# cp2101-esp32.net
KiCad netlist of a schematic drawn in EAGLE
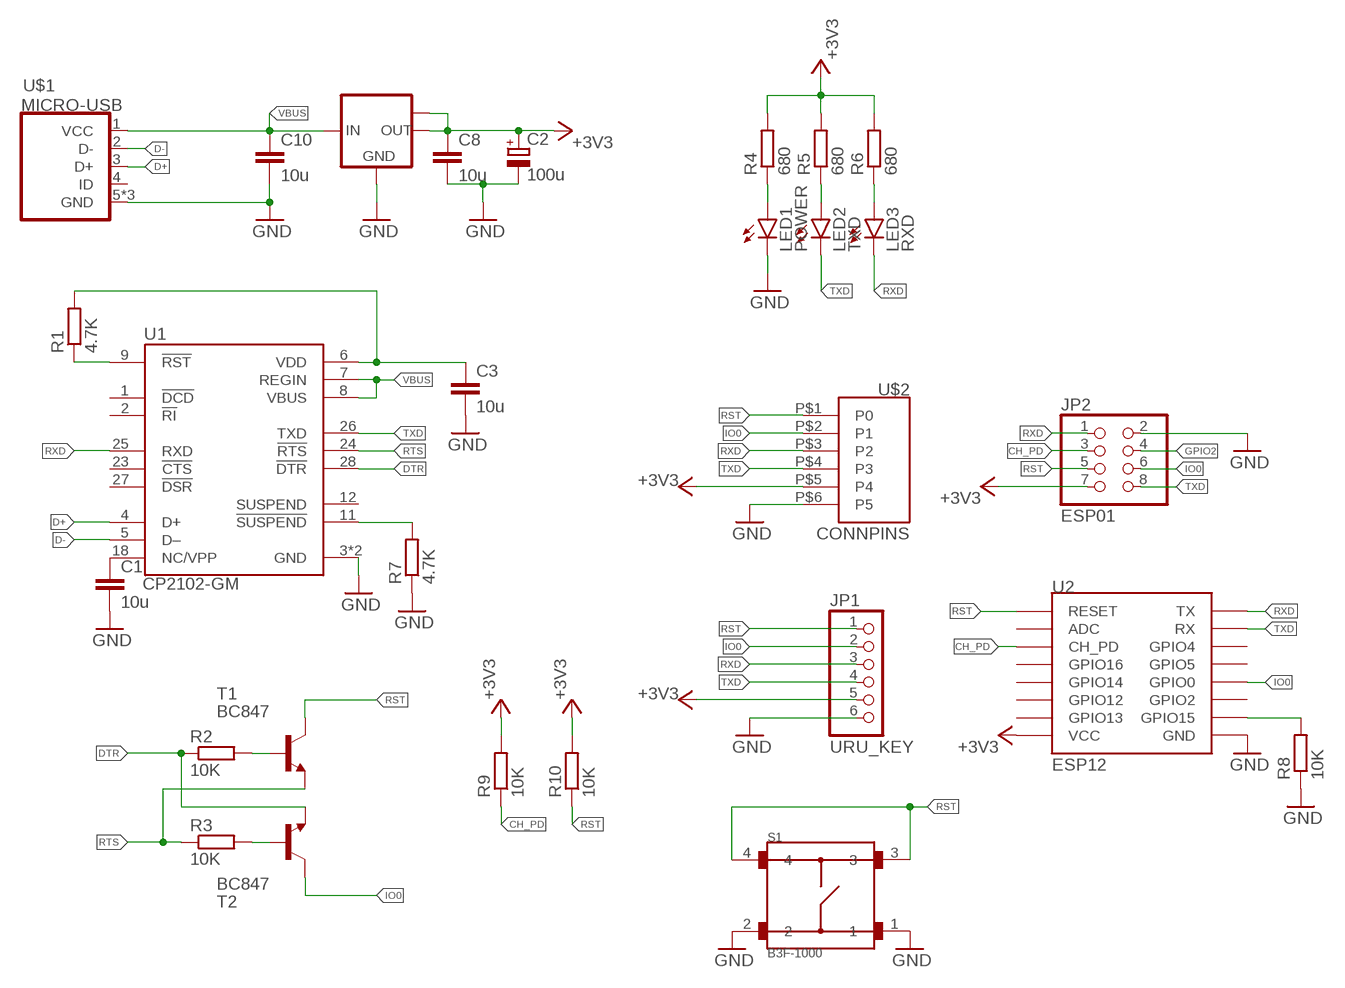
[diagram p0: schematic, sheet 1]

(export (version "E")
  (design (tool "Eeschema 10.0.6"))
  (components
    (comp (ref "C1")
      (value "10u")
      (footprint "eagle-import:C0805")
      (libsource (lib "eagle-import") (part "C-EUC0805"))
    )
    (comp (ref "C2")
      (value "100u")
      (footprint "eagle-import:A_3216-18R")
      (libsource (lib "eagle-import") (part "CPOL-EUA/3216-18R"))
    )
    (comp (ref "C3")
      (value "10u")
      (footprint "eagle-import:C0805")
      (libsource (lib "eagle-import") (part "C-EUC0805"))
    )
    (comp (ref "C8")
      (value "10u")
      (footprint "eagle-import:C0805")
      (libsource (lib "eagle-import") (part "C-EUC0805"))
    )
    (comp (ref "C10")
      (value "10u")
      (footprint "eagle-import:C0805")
      (libsource (lib "eagle-import") (part "C-EUC0805"))
    )
    (comp (ref "IC1")
      (value "LM1117MPX-3.3")
      (footprint "eagle-import:SOT223")
      (libsource (lib "eagle-import") (part "LM1117MPX-3.3"))
    )
    (comp (ref "JP1")
      (value "URU_KEY")
      (footprint "eagle-import:1X06_90")
      (libsource (lib "eagle-import") (part "PINHD-1X6/90"))
    )
    (comp (ref "JP2")
      (value "ESP01")
      (footprint "eagle-import:2X04")
      (libsource (lib "eagle-import") (part "PINHD-2X4"))
    )
    (comp (ref "LED1")
      (value "POWER")
      (footprint "eagle-import:CHIP-LED0805")
      (libsource (lib "eagle-import") (part "LEDCHIP-LED0805"))
    )
    (comp (ref "LED2")
      (value "TXD")
      (footprint "eagle-import:CHIP-LED0805")
      (libsource (lib "eagle-import") (part "LEDCHIP-LED0805"))
    )
    (comp (ref "LED3")
      (value "RXD")
      (footprint "eagle-import:CHIP-LED0805")
      (libsource (lib "eagle-import") (part "LEDCHIP-LED0805"))
    )
    (comp (ref "R1")
      (value "4.7K")
      (footprint "eagle-import:R0805")
      (libsource (lib "eagle-import") (part "R-EU_R0805"))
    )
    (comp (ref "R2")
      (value "10K")
      (footprint "eagle-import:R0805")
      (libsource (lib "eagle-import") (part "R-EU_R0805"))
    )
    (comp (ref "R3")
      (value "10K")
      (footprint "eagle-import:R0805")
      (libsource (lib "eagle-import") (part "R-EU_R0805"))
    )
    (comp (ref "R4")
      (value "680")
      (footprint "eagle-import:R0805")
      (libsource (lib "eagle-import") (part "R-EU_R0805"))
    )
    (comp (ref "R5")
      (value "680")
      (footprint "eagle-import:R0805")
      (libsource (lib "eagle-import") (part "R-EU_R0805"))
    )
    (comp (ref "R6")
      (value "680")
      (footprint "eagle-import:R0805")
      (libsource (lib "eagle-import") (part "R-EU_R0805"))
    )
    (comp (ref "R7")
      (value "4.7K")
      (footprint "eagle-import:R0805")
      (libsource (lib "eagle-import") (part "R-EU_R0805"))
    )
    (comp (ref "R8")
      (value "10K")
      (footprint "eagle-import:R0805")
      (libsource (lib "eagle-import") (part "R-EU_R0805"))
    )
    (comp (ref "R9")
      (value "10K")
      (footprint "eagle-import:R0805")
      (libsource (lib "eagle-import") (part "R-EU_R0805"))
    )
    (comp (ref "R10")
      (value "10K")
      (footprint "eagle-import:R0805")
      (libsource (lib "eagle-import") (part "R-EU_R0805"))
    )
    (comp (ref "S1")
      (value "B3F-1000")
      (footprint "eagle-import:SW_B3F-1000")
      (fields (field (name "MF") "Omron"))
      (libsource (lib "eagle-import") (part "B3F-1000"))
    )
    (comp (ref "T1")
      (value "BC847")
      (footprint "eagle-import:SOT23")
      (libsource (lib "eagle-import") (part "BC847"))
    )
    (comp (ref "T2")
      (value "BC847")
      (footprint "eagle-import:SOT23")
      (libsource (lib "eagle-import") (part "BC847"))
    )
    (comp (ref "U$1")
      (value "MICRO-USB")
      (footprint "eagle-import:MICRO-USB")
      (libsource (lib "eagle-import") (part "MICRO-USB"))
    )
    (comp (ref "U$2")
      (value "CONNPINS")
      (footprint "eagle-import:PINS")
      (libsource (lib "eagle-import") (part "CONNPINS"))
    )
    (comp (ref "U1")
      (value "CP2102-GM")
      (footprint "eagle-import:QFN50P500X500X100-29N")
      (fields (field (name "MF") "Silicon Labs"))
      (libsource (lib "eagle-import") (part "CP2102-GM"))
    )
    (comp (ref "U2")
      (value "ESP12")
      (footprint "eagle-import:ESP12")
      (libsource (lib "eagle-import") (part "ESP12"))
    )
  )
  (nets
    (net (code "1") (name "+3V3") (class "Default")
      (node (ref "C2") (pin "+") (pinfunction "+_+") (pintype "passive"))
      (node (ref "C8") (pin "1") (pinfunction "1_1") (pintype "passive"))
      (node (ref "IC1") (pin "2") (pinfunction "OUT_2") (pintype "passive"))
      (node (ref "IC1") (pin "TAB") (pinfunction "OUT1_TAB") (pintype "passive"))
      (node (ref "JP1") (pin "5") (pinfunction "5_5") (pintype "passive"))
      (node (ref "JP2") (pin "7") (pinfunction "7_7") (pintype "passive"))
      (node (ref "R10") (pin "2") (pinfunction "2_2") (pintype "passive"))
      (node (ref "R4") (pin "2") (pinfunction "2_2") (pintype "passive"))
      (node (ref "R5") (pin "2") (pinfunction "2_2") (pintype "passive"))
      (node (ref "R6") (pin "2") (pinfunction "2_2") (pintype "passive"))
      (node (ref "R9") (pin "2") (pinfunction "2_2") (pintype "passive"))
      (node (ref "U$2") (pin "P$5") (pinfunction "P4_P$5") (pintype "bidirectional"))
      (node (ref "U2") (pin "VCC") (pinfunction "VCC_VCC") (pintype "bidirectional"))
    )
    (net (code "2") (name "CH_PD") (class "Default")
      (node (ref "JP2") (pin "3") (pinfunction "3_3") (pintype "passive"))
      (node (ref "R9") (pin "1") (pinfunction "1_1") (pintype "passive"))
      (node (ref "U2") (pin "CH_PD") (pinfunction "CH_PD_CH_PD") (pintype "bidirectional"))
    )
    (net (code "3") (name "D+") (class "Default")
      (node (ref "U$1") (pin "3") (pinfunction "D+_3") (pintype "bidirectional"))
      (node (ref "U1") (pin "4") (pinfunction "D+_4") (pintype "bidirectional"))
    )
    (net (code "4") (name "D-") (class "Default")
      (node (ref "U$1") (pin "2") (pinfunction "D-_2") (pintype "bidirectional"))
      (node (ref "U1") (pin "5") (pinfunction "D–_5") (pintype "bidirectional"))
    )
    (net (code "5") (name "DTR") (class "Default")
      (node (ref "R2") (pin "1") (pinfunction "1_1") (pintype "passive"))
      (node (ref "T2") (pin "2") (pinfunction "E_2") (pintype "passive"))
      (node (ref "U1") (pin "28") (pinfunction "~{DTR}_28") (pintype "output"))
    )
    (net (code "6") (name "GND") (class "Default")
      (node (ref "C1") (pin "2") (pinfunction "2_2") (pintype "passive"))
      (node (ref "C10") (pin "2") (pinfunction "2_2") (pintype "passive"))
      (node (ref "C2") (pin "-") (pinfunction "-_-") (pintype "passive"))
      (node (ref "C3") (pin "2") (pinfunction "2_2") (pintype "passive"))
      (node (ref "C8") (pin "2") (pinfunction "2_2") (pintype "passive"))
      (node (ref "IC1") (pin "1") (pinfunction "GND_1") (pintype "input"))
      (node (ref "JP1") (pin "6") (pinfunction "6_6") (pintype "passive"))
      (node (ref "JP2") (pin "2") (pinfunction "2_2") (pintype "passive"))
      (node (ref "LED1") (pin "C") (pinfunction "C_C") (pintype "passive"))
      (node (ref "R7") (pin "1") (pinfunction "1_1") (pintype "passive"))
      (node (ref "R8") (pin "1") (pinfunction "1_1") (pintype "passive"))
      (node (ref "S1") (pin "1") (pinfunction "1_1") (pintype "passive"))
      (node (ref "S1") (pin "2") (pinfunction "2_2") (pintype "passive"))
      (node (ref "U$1") (pin "5") (pinfunction "GND_5") (pintype "power_in"))
      (node (ref "U$1") (pin "GND1") (pinfunction "GND_GND1") (pintype "power_in"))
      (node (ref "U$1") (pin "GND2") (pinfunction "GND_GND2") (pintype "power_in"))
      (node (ref "U$2") (pin "P$6") (pinfunction "P5_P$6") (pintype "bidirectional"))
      (node (ref "U1") (pin "29") (pinfunction "GND_29") (pintype "power_in"))
      (node (ref "U1") (pin "3") (pinfunction "GND_3") (pintype "power_in"))
      (node (ref "U2") (pin "GND") (pinfunction "GND_GND") (pintype "bidirectional"))
    )
    (net (code "7") (name "GPIO2") (class "Default")
      (node (ref "JP2") (pin "4") (pinfunction "4_4") (pintype "passive"))
    )
    (net (code "8") (name "IO0") (class "Default")
      (node (ref "JP1") (pin "2") (pinfunction "2_2") (pintype "passive"))
      (node (ref "JP2") (pin "6") (pinfunction "6_6") (pintype "passive"))
      (node (ref "T2") (pin "3") (pinfunction "C_3") (pintype "passive"))
      (node (ref "U$2") (pin "P$2") (pinfunction "P1_P$2") (pintype "bidirectional"))
      (node (ref "U2") (pin "GPIO0") (pinfunction "GPIO0_GPIO0") (pintype "bidirectional"))
    )
    (net (code "9") (name "Net-(LED1-PadA)") (class "Default")
      (node (ref "LED1") (pin "A") (pinfunction "A_A") (pintype "passive"))
      (node (ref "R4") (pin "1") (pinfunction "1_1") (pintype "passive"))
    )
    (net (code "10") (name "Net-(LED2-PadA)") (class "Default")
      (node (ref "LED2") (pin "A") (pinfunction "A_A") (pintype "passive"))
      (node (ref "R5") (pin "1") (pinfunction "1_1") (pintype "passive"))
    )
    (net (code "11") (name "Net-(LED3-PadA)") (class "Default")
      (node (ref "LED3") (pin "A") (pinfunction "A_A") (pintype "passive"))
      (node (ref "R6") (pin "1") (pinfunction "1_1") (pintype "passive"))
    )
    (net (code "12") (name "Net-(R8-Pad2)") (class "Default")
      (node (ref "R8") (pin "2") (pinfunction "2_2") (pintype "passive"))
      (node (ref "U2") (pin "GPIO15") (pinfunction "GPIO15_GPIO15") (pintype "bidirectional"))
    )
    (net (code "13") (name "Net-(T1-B)") (class "Default")
      (node (ref "R2") (pin "2") (pinfunction "2_2") (pintype "passive"))
      (node (ref "T1") (pin "1") (pinfunction "B_1") (pintype "passive"))
    )
    (net (code "14") (name "Net-(T2-B)") (class "Default")
      (node (ref "R3") (pin "2") (pinfunction "2_2") (pintype "passive"))
      (node (ref "T2") (pin "1") (pinfunction "B_1") (pintype "passive"))
    )
    (net (code "15") (name "Net-(U1-NC{slash}VPP)") (class "Default")
      (node (ref "C1") (pin "1") (pinfunction "1_1") (pintype "passive"))
      (node (ref "U1") (pin "18") (pinfunction "NC/VPP_18") (pintype "bidirectional"))
    )
    (net (code "16") (name "Net-(U1-VDD)") (class "Default")
      (node (ref "C3") (pin "1") (pinfunction "1_1") (pintype "passive"))
      (node (ref "R1") (pin "2") (pinfunction "2_2") (pintype "passive"))
      (node (ref "U1") (pin "6") (pinfunction "VDD_6") (pintype "power_in"))
    )
    (net (code "17") (name "Net-(U1-~{RST})") (class "Default")
      (node (ref "R1") (pin "1") (pinfunction "1_1") (pintype "passive"))
      (node (ref "U1") (pin "9") (pinfunction "~{RST}_9") (pintype "bidirectional"))
    )
    (net (code "18") (name "Net-(U1-~{SUSPEND})") (class "Default")
      (node (ref "R7") (pin "2") (pinfunction "2_2") (pintype "passive"))
      (node (ref "U1") (pin "11") (pinfunction "~{SUSPEND}_11") (pintype "output"))
    )
    (net (code "19") (name "RST") (class "Default")
      (node (ref "JP1") (pin "1") (pinfunction "1_1") (pintype "passive"))
      (node (ref "JP2") (pin "5") (pinfunction "5_5") (pintype "passive"))
      (node (ref "R10") (pin "1") (pinfunction "1_1") (pintype "passive"))
      (node (ref "S1") (pin "3") (pinfunction "3_3") (pintype "passive"))
      (node (ref "S1") (pin "4") (pinfunction "4_4") (pintype "passive"))
      (node (ref "T1") (pin "3") (pinfunction "C_3") (pintype "passive"))
      (node (ref "U$2") (pin "P$1") (pinfunction "P0_P$1") (pintype "bidirectional"))
      (node (ref "U2") (pin "RESET") (pinfunction "RESET_RESET") (pintype "bidirectional"))
    )
    (net (code "20") (name "RTS") (class "Default")
      (node (ref "R3") (pin "1") (pinfunction "1_1") (pintype "passive"))
      (node (ref "T1") (pin "2") (pinfunction "E_2") (pintype "passive"))
      (node (ref "U1") (pin "24") (pinfunction "~{RTS}_24") (pintype "output"))
    )
    (net (code "21") (name "RXD") (class "Default")
      (node (ref "JP1") (pin "3") (pinfunction "3_3") (pintype "passive"))
      (node (ref "JP2") (pin "1") (pinfunction "1_1") (pintype "passive"))
      (node (ref "LED3") (pin "C") (pinfunction "C_C") (pintype "passive"))
      (node (ref "U$2") (pin "P$3") (pinfunction "P2_P$3") (pintype "bidirectional"))
      (node (ref "U1") (pin "25") (pinfunction "RXD_25") (pintype "input"))
      (node (ref "U2") (pin "TX") (pinfunction "TX_TX") (pintype "bidirectional"))
    )
    (net (code "22") (name "TXD") (class "Default")
      (node (ref "JP1") (pin "4") (pinfunction "4_4") (pintype "passive"))
      (node (ref "JP2") (pin "8") (pinfunction "8_8") (pintype "passive"))
      (node (ref "LED2") (pin "C") (pinfunction "C_C") (pintype "passive"))
      (node (ref "U$2") (pin "P$4") (pinfunction "P3_P$4") (pintype "bidirectional"))
      (node (ref "U1") (pin "26") (pinfunction "TXD_26") (pintype "output"))
      (node (ref "U2") (pin "RX") (pinfunction "RX_RX") (pintype "bidirectional"))
    )
    (net (code "23") (name "VBUS") (class "Default")
      (node (ref "C10") (pin "1") (pinfunction "1_1") (pintype "passive"))
      (node (ref "IC1") (pin "3") (pinfunction "IN_3") (pintype "input"))
      (node (ref "U$1") (pin "1") (pinfunction "VCC_1") (pintype "power_in"))
      (node (ref "U1") (pin "7") (pinfunction "REGIN_7") (pintype "power_in"))
      (node (ref "U1") (pin "8") (pinfunction "VBUS_8") (pintype "power_in"))
    )
    (net (code "24") (name "unconnected-(U$1-ID-Pad4)") (class "Default")
      (node (ref "U$1") (pin "4") (pinfunction "ID_4") (pintype "bidirectional"))
    )
    (net (code "25") (name "unconnected-(U1-SUSPEND-Pad12)") (class "Default")
      (node (ref "U1") (pin "12") (pinfunction "SUSPEND_12") (pintype "output"))
    )
    (net (code "26") (name "unconnected-(U1-~{CTS}-Pad23)") (class "Default")
      (node (ref "U1") (pin "23") (pinfunction "~{CTS}_23") (pintype "input"))
    )
    (net (code "27") (name "unconnected-(U1-~{DCD}-Pad1)") (class "Default")
      (node (ref "U1") (pin "1") (pinfunction "~{DCD}_1") (pintype "input"))
    )
    (net (code "28") (name "unconnected-(U1-~{DSR}-Pad27)") (class "Default")
      (node (ref "U1") (pin "27") (pinfunction "~{DSR}_27") (pintype "input"))
    )
    (net (code "29") (name "unconnected-(U1-~{RI}-Pad2)") (class "Default")
      (node (ref "U1") (pin "2") (pinfunction "~{RI}_2") (pintype "input"))
    )
    (net (code "30") (name "unconnected-(U2-PadADC)") (class "Default")
      (node (ref "U2") (pin "ADC") (pinfunction "ADC_ADC") (pintype "bidirectional"))
    )
    (net (code "31") (name "unconnected-(U2-PadGPIO2)") (class "Default")
      (node (ref "U2") (pin "GPIO2") (pinfunction "GPIO2_GPIO2") (pintype "bidirectional"))
    )
    (net (code "32") (name "unconnected-(U2-PadGPIO4)") (class "Default")
      (node (ref "U2") (pin "GPIO4") (pinfunction "GPIO4_GPIO4") (pintype "bidirectional"))
    )
    (net (code "33") (name "unconnected-(U2-PadGPIO5)") (class "Default")
      (node (ref "U2") (pin "GPIO5") (pinfunction "GPIO5_GPIO5") (pintype "bidirectional"))
    )
    (net (code "34") (name "unconnected-(U2-PadGPIO12)") (class "Default")
      (node (ref "U2") (pin "GPIO12") (pinfunction "GPIO12_GPIO12") (pintype "bidirectional"))
    )
    (net (code "35") (name "unconnected-(U2-PadGPIO13)") (class "Default")
      (node (ref "U2") (pin "GPIO13") (pinfunction "GPIO13_GPIO13") (pintype "bidirectional"))
    )
    (net (code "36") (name "unconnected-(U2-PadGPIO14)") (class "Default")
      (node (ref "U2") (pin "GPIO14") (pinfunction "GPIO14_GPIO14") (pintype "bidirectional"))
    )
    (net (code "37") (name "unconnected-(U2-PadGPIO16)") (class "Default")
      (node (ref "U2") (pin "GPIO16") (pinfunction "GPIO16_GPIO16") (pintype "bidirectional"))
    )
  )
)
